# PiInTheSky-Mainboard-v2_2.net
KiCad netlist of a schematic drawn in EAGLE
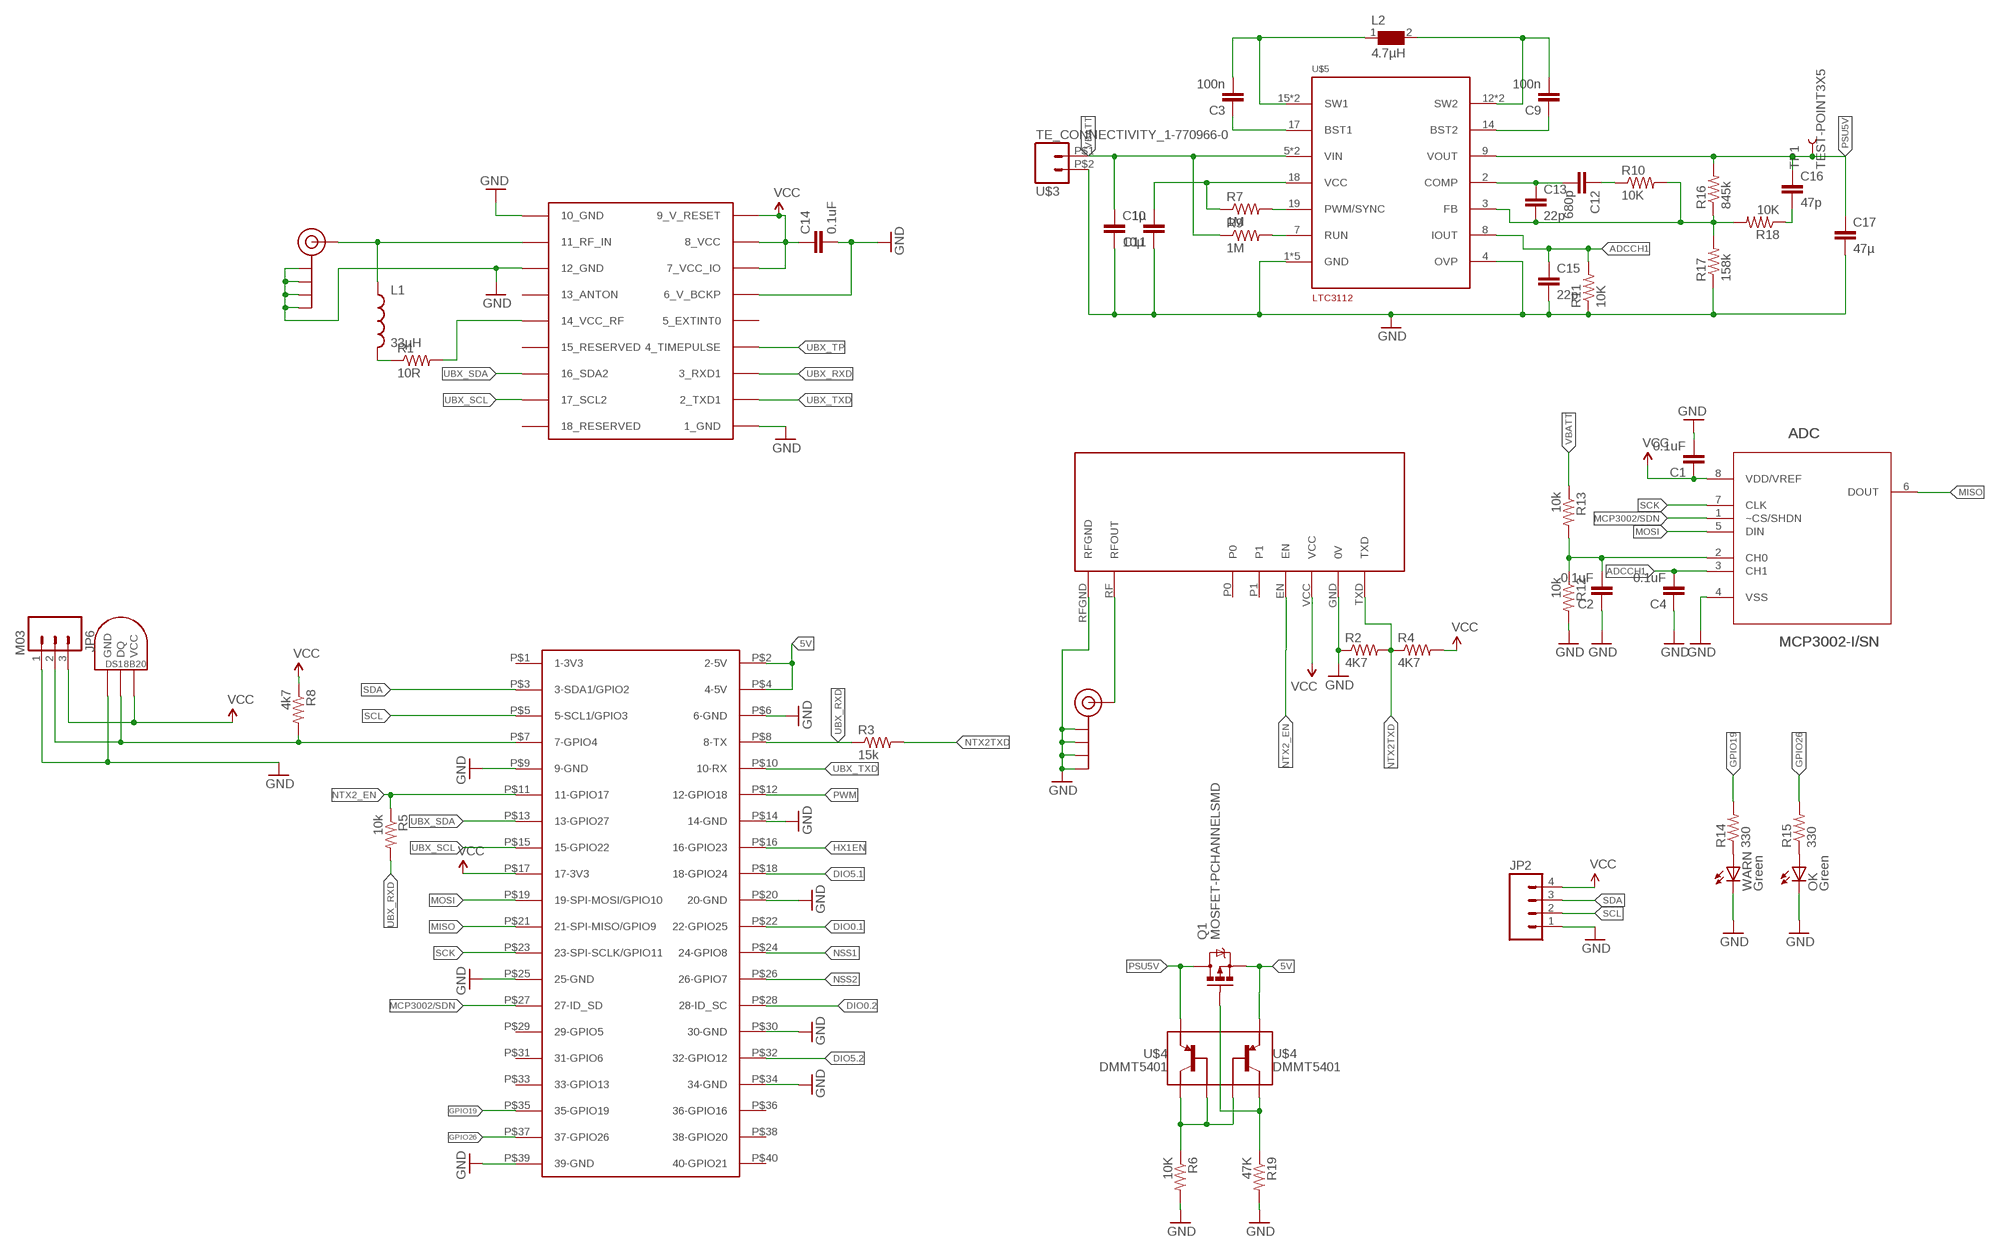
[diagram p0: schematic, sheet 1]

(export (version "E")
  (design (tool "Eeschema 10.0.6"))
  (components
    (comp (ref "ADC")
      (value "MCP3002-I/SN")
      (footprint "eagle-import:SOIC127P600X175-8N")
      (libsource (lib "eagle-import") (part "MCP3002-I/SN"))
    )
    (comp (ref "C1")
      (value "0.1uF")
      (footprint "eagle-import:0603-CAP")
      (libsource (lib "eagle-import") (part "CAP0603-CAP"))
    )
    (comp (ref "C2")
      (value "0.1uF")
      (footprint "eagle-import:0603-CAP")
      (libsource (lib "eagle-import") (part "CAP0603-CAP"))
    )
    (comp (ref "C3")
      (value "100n")
      (footprint "eagle-import:0603-CAP")
      (libsource (lib "eagle-import") (part "CAP0603-CAP"))
    )
    (comp (ref "C4")
      (value "0.1uF")
      (footprint "eagle-import:0603-CAP")
      (libsource (lib "eagle-import") (part "CAP0603-CAP"))
    )
    (comp (ref "C9")
      (value "100n")
      (footprint "eagle-import:0603-CAP")
      (libsource (lib "eagle-import") (part "CAP0603-CAP"))
    )
    (comp (ref "C10")
      (value "10µ")
      (footprint "eagle-import:1206")
      (libsource (lib "eagle-import") (part "CAP1206"))
    )
    (comp (ref "C11")
      (value "1µ")
      (footprint "eagle-import:0603-CAP")
      (libsource (lib "eagle-import") (part "CAP0603-CAP"))
    )
    (comp (ref "C12")
      (value "680p")
      (footprint "eagle-import:0603-CAP")
      (libsource (lib "eagle-import") (part "CAP0603-CAP"))
    )
    (comp (ref "C13")
      (value "22p")
      (footprint "eagle-import:0603-CAP")
      (libsource (lib "eagle-import") (part "CAP0603-CAP"))
    )
    (comp (ref "C14")
      (value "0.1uF")
      (footprint "eagle-import:0603-CAP")
      (libsource (lib "eagle-import") (part "CAP0603-CAP"))
    )
    (comp (ref "C15")
      (value "22p")
      (footprint "eagle-import:0603-CAP")
      (libsource (lib "eagle-import") (part "CAP0603-CAP"))
    )
    (comp (ref "C16")
      (value "47p")
      (footprint "eagle-import:0603-CAP")
      (libsource (lib "eagle-import") (part "CAP0603-CAP"))
    )
    (comp (ref "C17")
      (value "47µ")
      (footprint "eagle-import:1206")
      (libsource (lib "eagle-import") (part "CAP1206"))
    )
    (comp (ref "J$1")
      (value "SMA_EDGE")
      (footprint "eagle-import:SMA-EDGE")
      (libsource (lib "eagle-import") (part "SMA_EDGE"))
    )
    (comp (ref "J$2")
      (value "SMA_EDGE")
      (footprint "eagle-import:SMA-EDGE")
      (libsource (lib "eagle-import") (part "SMA_EDGE"))
    )
    (comp (ref "JP2")
      (value "M04PTH")
      (footprint "eagle-import:1X04")
      (libsource (lib "eagle-import") (part "M04PTH"))
    )
    (comp (ref "JP6")
      (value "M03")
      (footprint "eagle-import:M03-JST")
      (libsource (lib "eagle-import") (part "M03"))
    )
    (comp (ref "L1")
      (value "33µH")
      (footprint "eagle-import:0603")
      (libsource (lib "eagle-import") (part "INDUCTOR0603"))
    )
    (comp (ref "L2")
      (value "4.7µH")
      (footprint "eagle-import:WE-HCI_7030_7040_7050")
      (fields (field (name "MPN") "744311470"))
      (libsource (lib "eagle-import") (part "WE-HCI_7030/7040/7050-744311470"))
    )
    (comp (ref "OK")
      (value "Green")
      (footprint "eagle-import:LED-0603")
      (libsource (lib "eagle-import") (part "LED0603"))
    )
    (comp (ref "Q1")
      (value "MOSFET-PCHANNELSMD")
      (footprint "eagle-import:SOT23-3")
      (libsource (lib "eagle-import") (part "MOSFET-PCHANNELSMD"))
    )
    (comp (ref "R1")
      (value "10R")
      (footprint "eagle-import:0603-RES")
      (libsource (lib "eagle-import") (part "RESISTOR0603-RES"))
    )
    (comp (ref "R2")
      (value "4K7")
      (footprint "eagle-import:0603-RES")
      (libsource (lib "eagle-import") (part "RESISTOR0603-RES"))
    )
    (comp (ref "R3")
      (value "15k")
      (footprint "eagle-import:0603-RES")
      (libsource (lib "eagle-import") (part "RESISTOR0603-RES"))
    )
    (comp (ref "R4")
      (value "4K7")
      (footprint "eagle-import:0603-RES")
      (libsource (lib "eagle-import") (part "RESISTOR0603-RES"))
    )
    (comp (ref "R5")
      (value "10k")
      (footprint "eagle-import:0603-RES")
      (libsource (lib "eagle-import") (part "RESISTOR0603-RES"))
    )
    (comp (ref "R6")
      (value "10K")
      (footprint "eagle-import:0603-RES")
      (libsource (lib "eagle-import") (part "RESISTOR0603-RES"))
    )
    (comp (ref "R7")
      (value "1M")
      (footprint "eagle-import:0603-RES")
      (libsource (lib "eagle-import") (part "RESISTOR0603-RES"))
    )
    (comp (ref "R8")
      (value "4k7")
      (footprint "eagle-import:0603-RES")
      (libsource (lib "eagle-import") (part "RESISTOR0603-RES"))
    )
    (comp (ref "R9")
      (value "1M")
      (footprint "eagle-import:0603-RES")
      (libsource (lib "eagle-import") (part "RESISTOR0603-RES"))
    )
    (comp (ref "R10")
      (value "10K")
      (footprint "eagle-import:0603-RES")
      (libsource (lib "eagle-import") (part "RESISTOR0603-RES"))
    )
    (comp (ref "R11")
      (value "10K")
      (footprint "eagle-import:0603-RES")
      (libsource (lib "eagle-import") (part "RESISTOR0603-RES"))
    )
    (comp (ref "R12")
      (value "10k")
      (footprint "eagle-import:0603-RES")
      (libsource (lib "eagle-import") (part "RESISTOR0603-RES"))
    )
    (comp (ref "R13")
      (value "10k")
      (footprint "eagle-import:0603-RES")
      (libsource (lib "eagle-import") (part "RESISTOR0603-RES"))
    )
    (comp (ref "R14")
      (value "330")
      (footprint "eagle-import:0603-RES")
      (libsource (lib "eagle-import") (part "RESISTOR0603-RES"))
    )
    (comp (ref "R15")
      (value "330")
      (footprint "eagle-import:0603-RES")
      (libsource (lib "eagle-import") (part "RESISTOR0603-RES"))
    )
    (comp (ref "R16")
      (value "845k")
      (footprint "eagle-import:0603-RES")
      (libsource (lib "eagle-import") (part "RESISTOR0603-RES"))
    )
    (comp (ref "R17")
      (value "158k")
      (footprint "eagle-import:0603-RES")
      (libsource (lib "eagle-import") (part "RESISTOR0603-RES"))
    )
    (comp (ref "R18")
      (value "10K")
      (footprint "eagle-import:0603-RES")
      (libsource (lib "eagle-import") (part "RESISTOR0603-RES"))
    )
    (comp (ref "R19")
      (value "47K")
      (footprint "eagle-import:0603-RES")
      (libsource (lib "eagle-import") (part "RESISTOR0603-RES"))
    )
    (comp (ref "TEMP")
      (value "DS1821")
      (footprint "eagle-import:DS18B20_SOIC")
      (libsource (lib "eagle-import") (part "DS1820SOIC"))
    )
    (comp (ref "TP1")
      (value "TEST-POINT3X5")
      (footprint "eagle-import:PAD.03X.05")
      (libsource (lib "eagle-import") (part "TEST-POINT3X5"))
    )
    (comp (ref "U$1")
      (value "RASPBERRY-PI+")
      (footprint "eagle-import:RASPBERRY-PI-PLUS-CAM_NOTCH")
      (libsource (lib "eagle-import") (part "RASPBERRY-PI+"))
    )
    (comp (ref "U$3")
      (value "TE_CONNECTIVITY_1-770966-0")
      (footprint "eagle-import:TE_CONNECTIVITY_1-770966-0")
      (libsource (lib "eagle-import") (part "TE_CONNECTIVITY_1-770966-0"))
    )
    (comp (ref "U$4")
      (value "DMMT5401")
      (footprint "eagle-import:SOT26")
      (libsource (lib "eagle-import") (part "DMMT5401"))
    )
    (comp (ref "U$5")
      (value "LTC3112")
      (footprint "eagle-import:TSSOP-20")
      (libsource (lib "eagle-import") (part "LTC3112"))
    )
    (comp (ref "U$7")
      (value "UBLOX_MAX")
      (footprint "eagle-import:UBLOX_MAX")
      (libsource (lib "eagle-import") (part "UBLOX_MAX"))
    )
    (comp (ref "U$8")
      (value "RADIOMETRIX-MTX2")
      (footprint "eagle-import:RADIOMETRIX-MTX2")
      (libsource (lib "eagle-import") (part "RADIOMETRIX-MTX2"))
    )
    (comp (ref "WARN")
      (value "Green")
      (footprint "eagle-import:LED-0603")
      (libsource (lib "eagle-import") (part "LED0603"))
    )
  )
  (nets
    (net (code "1") (name "5V") (class "Default")
      (node (ref "Q1") (pin "2") (pinfunction "S_2") (pintype "passive"))
      (node (ref "U$1") (pin "P$2") (pinfunction "2-5V_P$2") (pintype "bidirectional"))
      (node (ref "U$1") (pin "P$4") (pinfunction "4-5V_P$4") (pintype "bidirectional"))
      (node (ref "U$4") (pin "5") (pinfunction "E2_5") (pintype "passive"))
    )
    (net (code "2") (name "ADCCH1") (class "Default")
      (node (ref "ADC") (pin "3") (pinfunction "CH1_3") (pintype "input"))
      (node (ref "C15") (pin "1") (pinfunction "1_1") (pintype "passive"))
      (node (ref "C4") (pin "2") (pinfunction "2_2") (pintype "passive"))
      (node (ref "R11") (pin "2") (pinfunction "2_2") (pintype "passive"))
      (node (ref "U$5") (pin "8") (pinfunction "IOUT_8") (pintype "bidirectional"))
    )
    (net (code "3") (name "DIO0.1") (class "Default")
      (node (ref "U$1") (pin "P$22") (pinfunction "22-GPIO25_P$22") (pintype "bidirectional"))
    )
    (net (code "4") (name "DIO0.2") (class "Default")
      (node (ref "U$1") (pin "P$28") (pinfunction "28-ID_SC_P$28") (pintype "bidirectional"))
    )
    (net (code "5") (name "DIO5.1") (class "Default")
      (node (ref "U$1") (pin "P$18") (pinfunction "18-GPIO24_P$18") (pintype "bidirectional"))
    )
    (net (code "6") (name "DIO5.2") (class "Default")
      (node (ref "U$1") (pin "P$32") (pinfunction "32-GPIO12_P$32") (pintype "bidirectional"))
    )
    (net (code "7") (name "GND") (class "Default")
      (node (ref "ADC") (pin "4") (pinfunction "VSS_4") (pintype "power_in"))
      (node (ref "C1") (pin "2") (pinfunction "2_2") (pintype "passive"))
      (node (ref "C10") (pin "2") (pinfunction "2_2") (pintype "passive"))
      (node (ref "C11") (pin "1") (pinfunction "1_1") (pintype "passive"))
      (node (ref "C14") (pin "2") (pinfunction "2_2") (pintype "passive"))
      (node (ref "C15") (pin "2") (pinfunction "2_2") (pintype "passive"))
      (node (ref "C17") (pin "2") (pinfunction "2_2") (pintype "passive"))
      (node (ref "C2") (pin "1") (pinfunction "1_1") (pintype "passive"))
      (node (ref "C4") (pin "1") (pinfunction "1_1") (pintype "passive"))
      (node (ref "J$1") (pin "GND@0") (pinfunction "GND_GND@0") (pintype "bidirectional"))
      (node (ref "J$1") (pin "GND@1") (pinfunction "GND_GND@1") (pintype "bidirectional"))
      (node (ref "J$1") (pin "GND@2") (pinfunction "GND_GND@2") (pintype "bidirectional"))
      (node (ref "J$1") (pin "GND@3") (pinfunction "GND_GND@3") (pintype "bidirectional"))
      (node (ref "J$2") (pin "GND@0") (pinfunction "GND_GND@0") (pintype "bidirectional"))
      (node (ref "J$2") (pin "GND@1") (pinfunction "GND_GND@1") (pintype "bidirectional"))
      (node (ref "J$2") (pin "GND@2") (pinfunction "GND_GND@2") (pintype "bidirectional"))
      (node (ref "J$2") (pin "GND@3") (pinfunction "GND_GND@3") (pintype "bidirectional"))
      (node (ref "JP2") (pin "1") (pinfunction "1_1") (pintype "passive"))
      (node (ref "JP6") (pin "1") (pinfunction "1_1") (pintype "passive"))
      (node (ref "OK") (pin "C") (pinfunction "C_C") (pintype "passive"))
      (node (ref "R11") (pin "1") (pinfunction "1_1") (pintype "passive"))
      (node (ref "R12") (pin "2") (pinfunction "2_2") (pintype "passive"))
      (node (ref "R17") (pin "1") (pinfunction "1_1") (pintype "passive"))
      (node (ref "R19") (pin "2") (pinfunction "2_2") (pintype "passive"))
      (node (ref "R2") (pin "1") (pinfunction "1_1") (pintype "passive"))
      (node (ref "R6") (pin "2") (pinfunction "2_2") (pintype "passive"))
      (node (ref "TEMP") (pin "GND") (pinfunction "GND_GND") (pintype "power_in"))
      (node (ref "U$1") (pin "P$14") (pinfunction "14-GND_P$14") (pintype "bidirectional"))
      (node (ref "U$1") (pin "P$20") (pinfunction "20-GND_P$20") (pintype "bidirectional"))
      (node (ref "U$1") (pin "P$25") (pinfunction "25-GND_P$25") (pintype "bidirectional"))
      (node (ref "U$1") (pin "P$30") (pinfunction "30-GND_P$30") (pintype "bidirectional"))
      (node (ref "U$1") (pin "P$34") (pinfunction "34-GND_P$34") (pintype "bidirectional"))
      (node (ref "U$1") (pin "P$39") (pinfunction "39-GND_P$39") (pintype "bidirectional"))
      (node (ref "U$1") (pin "P$6") (pinfunction "6-GND_P$6") (pintype "bidirectional"))
      (node (ref "U$1") (pin "P$9") (pinfunction "9-GND_P$9") (pintype "bidirectional"))
      (node (ref "U$3") (pin "P$2") (pinfunction "2_P$2") (pintype "passive"))
      (node (ref "U$5") (pin "1") (pinfunction "GND_1") (pintype "bidirectional"))
      (node (ref "U$5") (pin "10") (pinfunction "GND_10") (pintype "bidirectional"))
      (node (ref "U$5") (pin "11") (pinfunction "GND_11") (pintype "bidirectional"))
      (node (ref "U$5") (pin "20") (pinfunction "GND_20") (pintype "bidirectional"))
      (node (ref "U$5") (pin "21") (pinfunction "GND_21") (pintype "bidirectional"))
      (node (ref "U$5") (pin "4") (pinfunction "OVP_4") (pintype "bidirectional"))
      (node (ref "U$7") (pin "10_GND") (pinfunction "10_GND_10_GND") (pintype "power_in"))
      (node (ref "U$7") (pin "12_GND") (pinfunction "12_GND_12_GND") (pintype "power_in"))
      (node (ref "U$7") (pin "1_GND") (pinfunction "1_GND_1_GND") (pintype "power_in"))
      (node (ref "U$7") (pin "6_V_BCKP") (pinfunction "6_V_BCKP_6_V_BCKP") (pintype "bidirectional"))
      (node (ref "U$8") (pin "GND") (pinfunction "0V_GND") (pintype "bidirectional"))
      (node (ref "U$8") (pin "RFGND") (pinfunction "RFGND_RFGND") (pintype "bidirectional"))
      (node (ref "WARN") (pin "C") (pinfunction "C_C") (pintype "passive"))
    )
    (net (code "8") (name "GPIO19") (class "Default")
      (node (ref "R14") (pin "2") (pinfunction "2_2") (pintype "passive"))
      (node (ref "U$1") (pin "P$35") (pinfunction "35-GPIO19_P$35") (pintype "bidirectional"))
    )
    (net (code "9") (name "GPIO26") (class "Default")
      (node (ref "R15") (pin "2") (pinfunction "2_2") (pintype "passive"))
      (node (ref "U$1") (pin "P$37") (pinfunction "37-GPIO26_P$37") (pintype "bidirectional"))
    )
    (net (code "10") (name "HX1EN") (class "Default")
      (node (ref "U$1") (pin "P$16") (pinfunction "16-GPIO23_P$16") (pintype "bidirectional"))
    )
    (net (code "11") (name "MCP3002{slash}SDN") (class "Default")
      (node (ref "ADC") (pin "1") (pinfunction "~{CS/SHDN}_1") (pintype "input"))
      (node (ref "U$1") (pin "P$27") (pinfunction "27-ID_SD_P$27") (pintype "bidirectional"))
    )
    (net (code "12") (name "MISO") (class "Default")
      (node (ref "ADC") (pin "6") (pinfunction "DOUT_6") (pintype "output"))
      (node (ref "U$1") (pin "P$21") (pinfunction "21-SPI-MISO/GPIO9_P$21") (pintype "bidirectional"))
    )
    (net (code "13") (name "MOSI") (class "Default")
      (node (ref "ADC") (pin "5") (pinfunction "DIN_5") (pintype "input"))
      (node (ref "U$1") (pin "P$19") (pinfunction "19-SPI-MOSI/GPIO10_P$19") (pintype "bidirectional"))
    )
    (net (code "14") (name "NSS1") (class "Default")
      (node (ref "U$1") (pin "P$24") (pinfunction "24-GPIO8_P$24") (pintype "bidirectional"))
    )
    (net (code "15") (name "NSS2") (class "Default")
      (node (ref "U$1") (pin "P$26") (pinfunction "26-GPIO7_P$26") (pintype "bidirectional"))
    )
    (net (code "16") (name "NTX2TXD") (class "Default")
      (node (ref "R2") (pin "2") (pinfunction "2_2") (pintype "passive"))
      (node (ref "R3") (pin "2") (pinfunction "2_2") (pintype "passive"))
      (node (ref "R4") (pin "1") (pinfunction "1_1") (pintype "passive"))
      (node (ref "U$8") (pin "TXD") (pinfunction "TXD_TXD") (pintype "bidirectional"))
    )
    (net (code "17") (name "NTX2_EN") (class "Default")
      (node (ref "R5") (pin "1") (pinfunction "1_1") (pintype "passive"))
      (node (ref "U$1") (pin "P$11") (pinfunction "11-GPIO17_P$11") (pintype "bidirectional"))
      (node (ref "U$8") (pin "EN") (pinfunction "EN_EN") (pintype "bidirectional"))
    )
    (net (code "18") (name "Net-(ADC-CH0)") (class "Default")
      (node (ref "ADC") (pin "2") (pinfunction "CH0_2") (pintype "input"))
      (node (ref "C2") (pin "2") (pinfunction "2_2") (pintype "passive"))
      (node (ref "R12") (pin "1") (pinfunction "1_1") (pintype "passive"))
      (node (ref "R13") (pin "2") (pinfunction "2_2") (pintype "passive"))
    )
    (net (code "19") (name "Net-(C3-Pad2)") (class "Default")
      (node (ref "C3") (pin "2") (pinfunction "2_2") (pintype "passive"))
      (node (ref "L2") (pin "1") (pinfunction "1_1") (pintype "passive"))
      (node (ref "U$5") (pin "15") (pinfunction "SW1_15") (pintype "bidirectional"))
      (node (ref "U$5") (pin "16") (pinfunction "SW1_16") (pintype "bidirectional"))
    )
    (net (code "20") (name "Net-(C9-Pad2)") (class "Default")
      (node (ref "C9") (pin "2") (pinfunction "2_2") (pintype "passive"))
      (node (ref "L2") (pin "2") (pinfunction "2_2") (pintype "passive"))
      (node (ref "U$5") (pin "12") (pinfunction "SW2_12") (pintype "bidirectional"))
      (node (ref "U$5") (pin "13") (pinfunction "SW2_13") (pintype "bidirectional"))
    )
    (net (code "21") (name "Net-(C12-Pad1)") (class "Default")
      (node (ref "C12") (pin "1") (pinfunction "1_1") (pintype "passive"))
      (node (ref "R10") (pin "1") (pinfunction "1_1") (pintype "passive"))
    )
    (net (code "22") (name "Net-(C16-Pad2)") (class "Default")
      (node (ref "C16") (pin "2") (pinfunction "2_2") (pintype "passive"))
      (node (ref "R18") (pin "1") (pinfunction "1_1") (pintype "passive"))
    )
    (net (code "23") (name "Net-(J$1-SIGNAL)") (class "Default")
      (node (ref "J$1") (pin "SIG") (pinfunction "SIGNAL_SIG") (pintype "bidirectional"))
      (node (ref "L1") (pin "1") (pinfunction "1_1") (pintype "passive"))
      (node (ref "U$7") (pin "11_RF_IN") (pinfunction "11_RF_IN_11_RF_IN") (pintype "bidirectional"))
    )
    (net (code "24") (name "Net-(J$2-SIGNAL)") (class "Default")
      (node (ref "J$2") (pin "SIG") (pinfunction "SIGNAL_SIG") (pintype "bidirectional"))
      (node (ref "U$8") (pin "RF") (pinfunction "RFOUT_RF") (pintype "bidirectional"))
    )
    (net (code "25") (name "Net-(L1-Pad2)") (class "Default")
      (node (ref "L1") (pin "2") (pinfunction "2_2") (pintype "passive"))
      (node (ref "R1") (pin "1") (pinfunction "1_1") (pintype "passive"))
    )
    (net (code "26") (name "Net-(OK-PadA)") (class "Default")
      (node (ref "OK") (pin "A") (pinfunction "A_A") (pintype "passive"))
      (node (ref "R15") (pin "1") (pinfunction "1_1") (pintype "passive"))
    )
    (net (code "27") (name "Net-(Q1-G)") (class "Default")
      (node (ref "Q1") (pin "1") (pinfunction "G_1") (pintype "passive"))
      (node (ref "R19") (pin "1") (pinfunction "1_1") (pintype "passive"))
      (node (ref "U$4") (pin "4") (pinfunction "C2_4") (pintype "passive"))
    )
    (net (code "28") (name "Net-(R1-Pad2)") (class "Default")
      (node (ref "R1") (pin "2") (pinfunction "2_2") (pintype "passive"))
      (node (ref "U$7") (pin "14_VCC_RF") (pinfunction "14_VCC_RF_14_VCC_RF") (pintype "bidirectional"))
    )
    (net (code "29") (name "Net-(R14-Pad1)") (class "Default")
      (node (ref "R14") (pin "1") (pinfunction "1_1") (pintype "passive"))
      (node (ref "WARN") (pin "A") (pinfunction "A_A") (pintype "passive"))
    )
    (net (code "30") (name "Net-(U$1-7-GPIO4)") (class "Default")
      (node (ref "JP6") (pin "2") (pinfunction "2_2") (pintype "passive"))
      (node (ref "R8") (pin "2") (pinfunction "2_2") (pintype "passive"))
      (node (ref "TEMP") (pin "DQ") (pinfunction "DQ_DQ") (pintype "bidirectional"))
      (node (ref "U$1") (pin "P$7") (pinfunction "7-GPIO4_P$7") (pintype "bidirectional"))
    )
    (net (code "31") (name "Net-(U$4-B1)") (class "Default")
      (node (ref "R6") (pin "1") (pinfunction "1_1") (pintype "passive"))
      (node (ref "U$4") (pin "1") (pinfunction "C1_1") (pintype "passive"))
      (node (ref "U$4") (pin "2") (pinfunction "B1_2") (pintype "passive"))
      (node (ref "U$4") (pin "3") (pinfunction "B2_3") (pintype "passive"))
    )
    (net (code "32") (name "Net-(U$5-BST1)") (class "Default")
      (node (ref "C3") (pin "1") (pinfunction "1_1") (pintype "passive"))
      (node (ref "U$5") (pin "17") (pinfunction "BST1_17") (pintype "bidirectional"))
    )
    (net (code "33") (name "Net-(U$5-BST2)") (class "Default")
      (node (ref "C9") (pin "1") (pinfunction "1_1") (pintype "passive"))
      (node (ref "U$5") (pin "14") (pinfunction "BST2_14") (pintype "bidirectional"))
    )
    (net (code "34") (name "Net-(U$5-COMP)") (class "Default")
      (node (ref "C12") (pin "2") (pinfunction "2_2") (pintype "passive"))
      (node (ref "C13") (pin "1") (pinfunction "1_1") (pintype "passive"))
      (node (ref "U$5") (pin "2") (pinfunction "COMP_2") (pintype "bidirectional"))
    )
    (net (code "35") (name "Net-(U$5-FB)") (class "Default")
      (node (ref "C13") (pin "2") (pinfunction "2_2") (pintype "passive"))
      (node (ref "R10") (pin "2") (pinfunction "2_2") (pintype "passive"))
      (node (ref "R16") (pin "1") (pinfunction "1_1") (pintype "passive"))
      (node (ref "R17") (pin "2") (pinfunction "2_2") (pintype "passive"))
      (node (ref "R18") (pin "2") (pinfunction "2_2") (pintype "passive"))
      (node (ref "U$5") (pin "3") (pinfunction "FB_3") (pintype "bidirectional"))
    )
    (net (code "36") (name "Net-(U$5-PWM{slash}SYNC)") (class "Default")
      (node (ref "R7") (pin "2") (pinfunction "2_2") (pintype "passive"))
      (node (ref "U$5") (pin "19") (pinfunction "PWM/SYNC_19") (pintype "bidirectional"))
    )
    (net (code "37") (name "Net-(U$5-RUN)") (class "Default")
      (node (ref "R9") (pin "2") (pinfunction "2_2") (pintype "passive"))
      (node (ref "U$5") (pin "7") (pinfunction "RUN_7") (pintype "bidirectional"))
    )
    (net (code "38") (name "Net-(U$5-VCC)") (class "Default")
      (node (ref "C11") (pin "2") (pinfunction "2_2") (pintype "passive"))
      (node (ref "R7") (pin "1") (pinfunction "1_1") (pintype "passive"))
      (node (ref "U$5") (pin "18") (pinfunction "VCC_18") (pintype "bidirectional"))
    )
    (net (code "39") (name "PSU5V") (class "Default")
      (node (ref "C16") (pin "1") (pinfunction "1_1") (pintype "passive"))
      (node (ref "C17") (pin "1") (pinfunction "1_1") (pintype "passive"))
      (node (ref "Q1") (pin "3") (pinfunction "D_3") (pintype "passive"))
      (node (ref "R16") (pin "2") (pinfunction "2_2") (pintype "passive"))
      (node (ref "TP1") (pin "P$1") (pinfunction "1_P$1") (pintype "bidirectional"))
      (node (ref "U$4") (pin "6") (pinfunction "E1_6") (pintype "passive"))
      (node (ref "U$5") (pin "9") (pinfunction "VOUT_9") (pintype "bidirectional"))
    )
    (net (code "40") (name "PWM") (class "Default")
      (node (ref "U$1") (pin "P$12") (pinfunction "12-GPIO18_P$12") (pintype "bidirectional"))
    )
    (net (code "41") (name "SCK") (class "Default")
      (node (ref "ADC") (pin "7") (pinfunction "CLK_7") (pintype "input"))
      (node (ref "U$1") (pin "P$23") (pinfunction "23-SPI-SCLK/GPIO11_P$23") (pintype "bidirectional"))
    )
    (net (code "42") (name "SCL") (class "Default")
      (node (ref "JP2") (pin "2") (pinfunction "2_2") (pintype "passive"))
      (node (ref "U$1") (pin "P$5") (pinfunction "5-SCL1/GPIO3_P$5") (pintype "bidirectional"))
    )
    (net (code "43") (name "SDA") (class "Default")
      (node (ref "JP2") (pin "3") (pinfunction "3_3") (pintype "passive"))
      (node (ref "U$1") (pin "P$3") (pinfunction "3-SDA1/GPIO2_P$3") (pintype "bidirectional"))
    )
    (net (code "44") (name "UBX_RXD") (class "Default")
      (node (ref "R3") (pin "1") (pinfunction "1_1") (pintype "passive"))
      (node (ref "R5") (pin "2") (pinfunction "2_2") (pintype "passive"))
      (node (ref "U$1") (pin "P$8") (pinfunction "8-TX_P$8") (pintype "bidirectional"))
      (node (ref "U$7") (pin "3_RXD1") (pinfunction "3_RXD1_3_RXD1") (pintype "bidirectional"))
    )
    (net (code "45") (name "UBX_SCL") (class "Default")
      (node (ref "U$1") (pin "P$15") (pinfunction "15-GPIO22_P$15") (pintype "bidirectional"))
      (node (ref "U$7") (pin "17_SCL2") (pinfunction "17_SCL2_17_SCL2") (pintype "bidirectional"))
    )
    (net (code "46") (name "UBX_SDA") (class "Default")
      (node (ref "U$1") (pin "P$13") (pinfunction "13-GPIO27_P$13") (pintype "bidirectional"))
      (node (ref "U$7") (pin "16_SDA2") (pinfunction "16_SDA2_16_SDA2") (pintype "bidirectional"))
    )
    (net (code "47") (name "UBX_TP") (class "Default")
      (node (ref "U$7") (pin "4_TIMEPULSE") (pinfunction "4_TIMEPULSE_4_TIMEPULSE") (pintype "bidirectional"))
    )
    (net (code "48") (name "UBX_TXD") (class "Default")
      (node (ref "U$1") (pin "P$10") (pinfunction "10-RX_P$10") (pintype "bidirectional"))
      (node (ref "U$7") (pin "2_TXD1") (pinfunction "2_TXD1_2_TXD1") (pintype "bidirectional"))
    )
    (net (code "49") (name "VBATT") (class "Default")
      (node (ref "C10") (pin "1") (pinfunction "1_1") (pintype "passive"))
      (node (ref "R13") (pin "1") (pinfunction "1_1") (pintype "passive"))
      (node (ref "R9") (pin "1") (pinfunction "1_1") (pintype "passive"))
      (node (ref "U$3") (pin "P$1") (pinfunction "1_P$1") (pintype "passive"))
      (node (ref "U$5") (pin "5") (pinfunction "VIN_5") (pintype "bidirectional"))
      (node (ref "U$5") (pin "6") (pinfunction "VIN_6") (pintype "bidirectional"))
    )
    (net (code "50") (name "VCC") (class "Default")
      (node (ref "ADC") (pin "8") (pinfunction "VDD/VREF_8") (pintype "power_in"))
      (node (ref "C1") (pin "1") (pinfunction "1_1") (pintype "passive"))
      (node (ref "C14") (pin "1") (pinfunction "1_1") (pintype "passive"))
      (node (ref "JP2") (pin "4") (pinfunction "4_4") (pintype "passive"))
      (node (ref "JP6") (pin "3") (pinfunction "3_3") (pintype "passive"))
      (node (ref "R4") (pin "2") (pinfunction "2_2") (pintype "passive"))
      (node (ref "R8") (pin "1") (pinfunction "1_1") (pintype "passive"))
      (node (ref "TEMP") (pin "VCC") (pinfunction "VCC_VCC") (pintype "power_in"))
      (node (ref "U$1") (pin "P$17") (pinfunction "17-3V3_P$17") (pintype "bidirectional"))
      (node (ref "U$7") (pin "7_VCC_IO") (pinfunction "7_VCC_IO_7_VCC_IO") (pintype "power_in"))
      (node (ref "U$7") (pin "8_VCC") (pinfunction "8_VCC_8_VCC") (pintype "power_in"))
      (node (ref "U$7") (pin "9_V_RESET") (pinfunction "9_V_RESET_9_V_RESET") (pintype "power_in"))
      (node (ref "U$8") (pin "VCC") (pinfunction "VCC_VCC") (pintype "bidirectional"))
    )
    (net (code "51") (name "unconnected-(U$1-1-3V3-PadP$1)") (class "Default")
      (node (ref "U$1") (pin "P$1") (pinfunction "1-3V3_P$1") (pintype "bidirectional"))
    )
    (net (code "52") (name "unconnected-(U$1-29-GPIO5-PadP$29)") (class "Default")
      (node (ref "U$1") (pin "P$29") (pinfunction "29-GPIO5_P$29") (pintype "bidirectional"))
    )
    (net (code "53") (name "unconnected-(U$1-31-GPIO6-PadP$31)") (class "Default")
      (node (ref "U$1") (pin "P$31") (pinfunction "31-GPIO6_P$31") (pintype "bidirectional"))
    )
    (net (code "54") (name "unconnected-(U$1-33-GPIO13-PadP$33)") (class "Default")
      (node (ref "U$1") (pin "P$33") (pinfunction "33-GPIO13_P$33") (pintype "bidirectional"))
    )
    (net (code "55") (name "unconnected-(U$1-36-GPIO16-PadP$36)") (class "Default")
      (node (ref "U$1") (pin "P$36") (pinfunction "36-GPIO16_P$36") (pintype "bidirectional"))
    )
    (net (code "56") (name "unconnected-(U$1-38-GPIO20-PadP$38)") (class "Default")
      (node (ref "U$1") (pin "P$38") (pinfunction "38-GPIO20_P$38") (pintype "bidirectional"))
    )
    (net (code "57") (name "unconnected-(U$1-40-GPIO21-PadP$40)") (class "Default")
      (node (ref "U$1") (pin "P$40") (pinfunction "40-GPIO21_P$40") (pintype "bidirectional"))
    )
    (net (code "58") (name "unconnected-(U$7-Pad5_EXTINT0)") (class "Default")
      (node (ref "U$7") (pin "5_EXTINT0") (pinfunction "5_EXTINT0_5_EXTINT0") (pintype "bidirectional"))
    )
    (net (code "59") (name "unconnected-(U$7-Pad13_ANTON)") (class "Default")
      (node (ref "U$7") (pin "13_ANTON") (pinfunction "13_ANTON_13_ANTON") (pintype "bidirectional"))
    )
    (net (code "60") (name "unconnected-(U$7-Pad15_RESERVED)") (class "Default")
      (node (ref "U$7") (pin "15_RESERVED") (pinfunction "15_RESERVED_15_RESERVED") (pintype "bidirectional"))
    )
    (net (code "61") (name "unconnected-(U$7-Pad18_RESERVED)") (class "Default")
      (node (ref "U$7") (pin "18_RESERVED") (pinfunction "18_RESERVED_18_RESERVED") (pintype "bidirectional"))
    )
    (net (code "62") (name "unconnected-(U$8-PadP0)") (class "Default")
      (node (ref "U$8") (pin "P0") (pinfunction "P0_P0") (pintype "bidirectional"))
    )
    (net (code "63") (name "unconnected-(U$8-PadP1)") (class "Default")
      (node (ref "U$8") (pin "P1") (pinfunction "P1_P1") (pintype "bidirectional"))
    )
  )
)
